# antipaparazzi.net
KiCad netlist of a schematic drawn in EAGLE
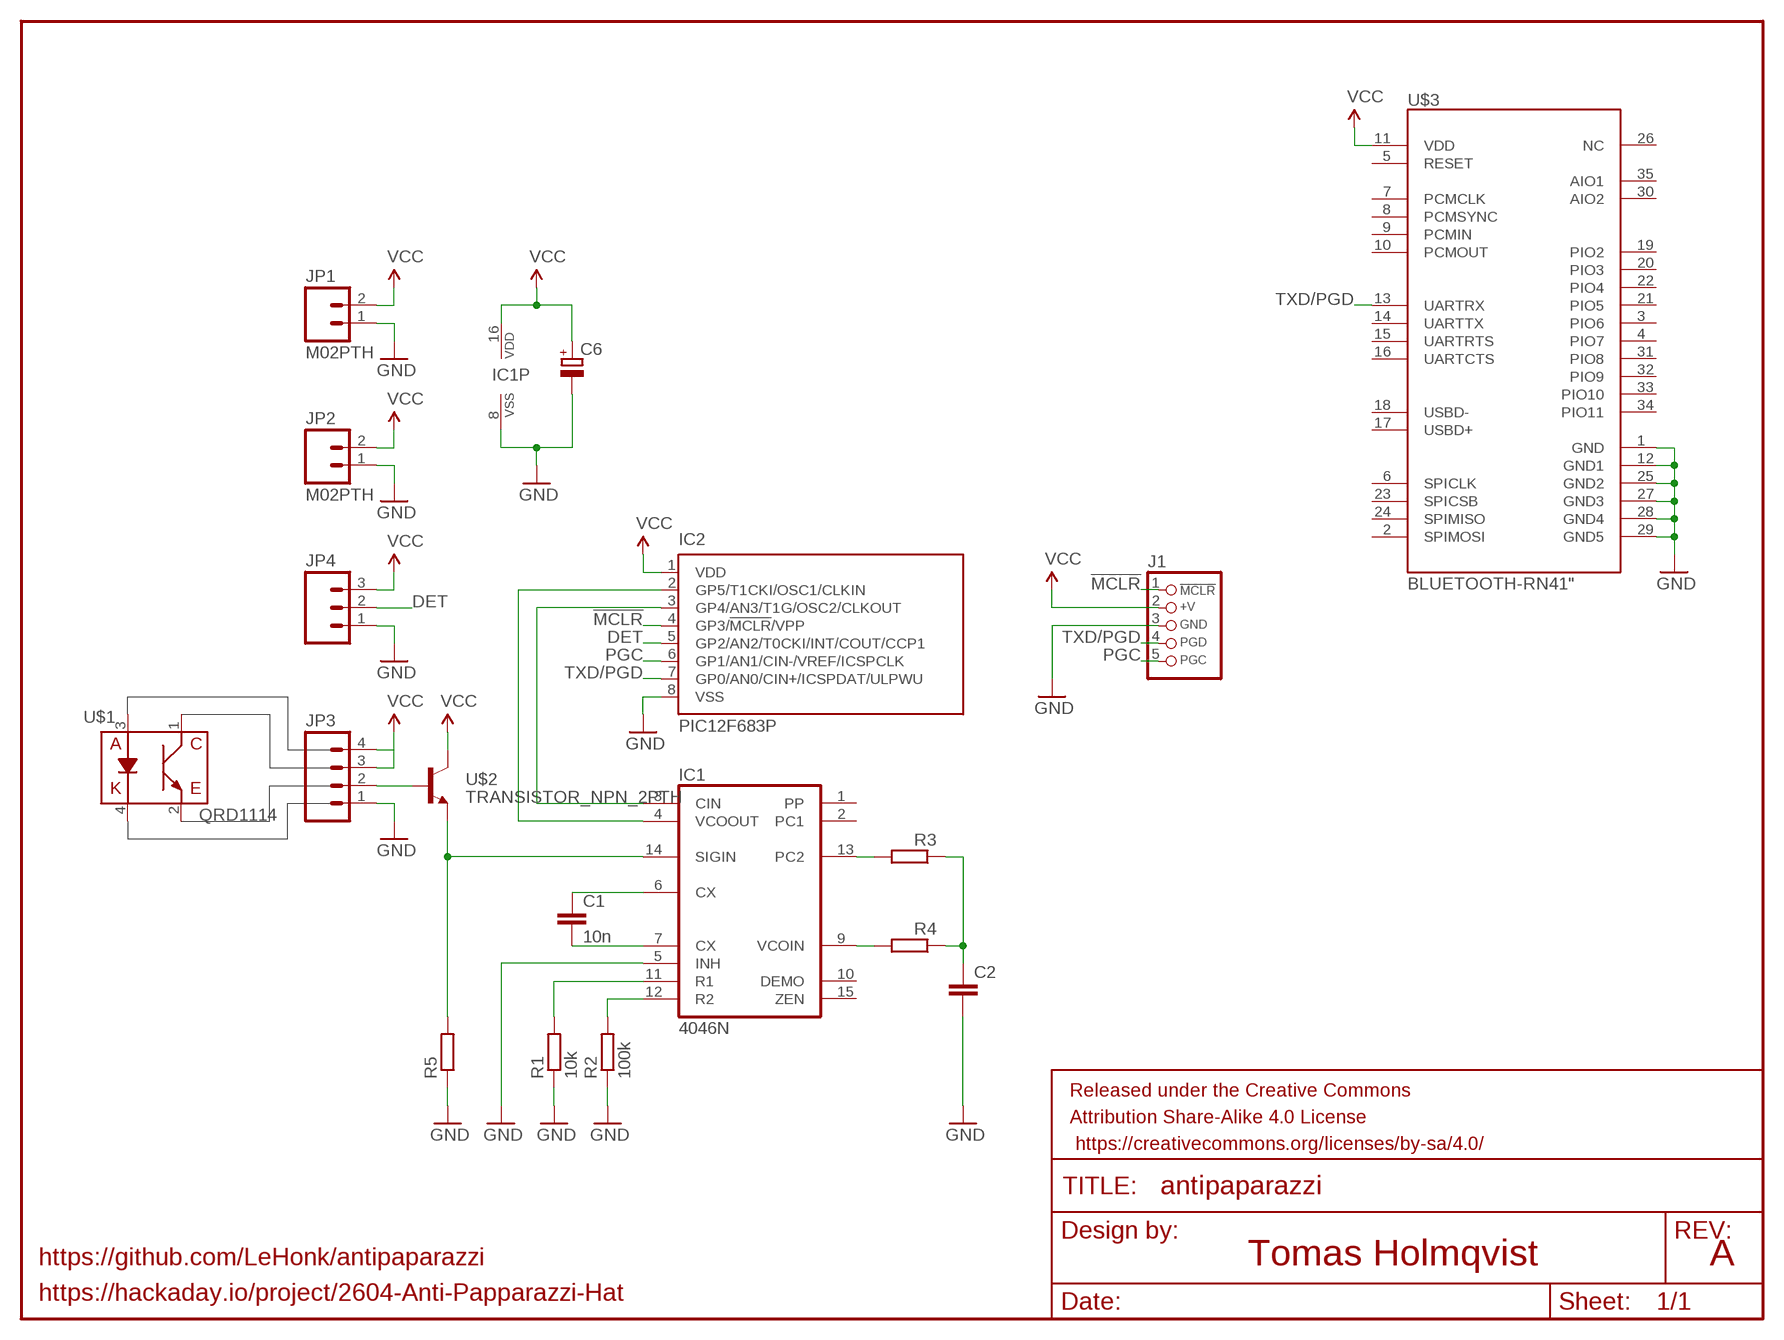
[diagram p0: schematic, sheet 1]

(export (version "E")
  (design (tool "Eeschema 10.0.6"))
  (components
    (comp (ref "C1")
      (value "10n")
      (footprint "eagle-import:C025_050-025X075")
      (libsource (lib "eagle-import") (part "C-EU025_050-025X075"))
    )
    (comp (ref "C2")
      (value "C-EU025_050-025X075")
      (footprint "eagle-import:C025_050-025X075")
      (libsource (lib "eagle-import") (part "C-EU025_050-025X075"))
    )
    (comp (ref "C6")
      (value "CPOL-EUE2.5-6")
      (footprint "eagle-import:E2,5-6")
      (libsource (lib "eagle-import") (part "CPOL-EUE2.5-6"))
    )
    (comp (ref "FRAME1")
      (value "FRAME-LETTER")
      (footprint "eagle-import:CREATIVE_COMMONS")
      (libsource (lib "eagle-import") (part "FRAME-LETTER"))
    )
    (comp (ref "IC1")
      (value "4046N")
      (footprint "eagle-import:DIL16")
      (libsource (lib "eagle-import") (part "4046N"))
    )
    (comp (ref "IC2")
      (value "PIC12F683P")
      (footprint "eagle-import:DIL8")
      (fields (field (name "MF") "MICROCHIP") (field (name "MPN") "PIC12F683-I/P"))
      (libsource (lib "eagle-import") (part "PIC12F683P"))
    )
    (comp (ref "J1")
      (value "CON_HEADER_PRG_PIC_ICSP0.1INCH_B")
      (footprint "eagle-import:HEADER_PRG_1X05_ICSP_B")
      (libsource (lib "eagle-import") (part "CON_HEADER_PRG_PIC_ICSP0.1INCH_B"))
    )
    (comp (ref "JP1")
      (value "M02PTH")
      (footprint "eagle-import:1X02")
      (libsource (lib "eagle-import") (part "M02PTH"))
    )
    (comp (ref "JP2")
      (value "M02PTH")
      (footprint "eagle-import:1X02")
      (libsource (lib "eagle-import") (part "M02PTH"))
    )
    (comp (ref "JP3")
      (value "M04PTH")
      (footprint "eagle-import:1X04")
      (libsource (lib "eagle-import") (part "M04PTH"))
    )
    (comp (ref "JP4")
      (value "M03PTH")
      (footprint "eagle-import:1X03")
      (libsource (lib "eagle-import") (part "M03PTH"))
    )
    (comp (ref "R1")
      (value "10k")
      (footprint "eagle-import:0207_2V")
      (libsource (lib "eagle-import") (part "R-EU_0207/2V"))
    )
    (comp (ref "R2")
      (value "100k")
      (footprint "eagle-import:0207_2V")
      (libsource (lib "eagle-import") (part "R-EU_0207/2V"))
    )
    (comp (ref "R3")
      (value "R-EU_0207/2V")
      (footprint "eagle-import:0207_2V")
      (libsource (lib "eagle-import") (part "R-EU_0207/2V"))
    )
    (comp (ref "R4")
      (value "R-EU_0207/2V")
      (footprint "eagle-import:0207_2V")
      (libsource (lib "eagle-import") (part "R-EU_0207/2V"))
    )
    (comp (ref "R5")
      (value "R-EU_0207/2V")
      (footprint "eagle-import:0207_2V")
      (libsource (lib "eagle-import") (part "R-EU_0207/2V"))
    )
    (comp (ref "U$1")
      (value "QRD1114")
      (footprint "eagle-import:QRD1114")
      (libsource (lib "eagle-import") (part "QRD1114"))
    )
    (comp (ref "U$2")
      (value "TRANSISTOR_NPN_2PTH")
      (footprint "eagle-import:TO-92")
      (libsource (lib "eagle-import") (part "TRANSISTOR_NPN_2PTH"))
    )
    (comp (ref "U$3")
      (value "BLUETOOTH-RN41\"")
      (footprint "eagle-import:RN41")
      (libsource (lib "eagle-import") (part "BLUETOOTH-RN41{dblquote}"))
    )
  )
  (nets
    (net (code "1") (name "/DET") (class "Default")
      (node (ref "IC2") (pin "5") (pinfunction "GP2/AN2/T0CKI/INT/COUT/CCP1_5") (pintype "bidirectional"))
      (node (ref "JP4") (pin "2") (pinfunction "2_2") (pintype "passive"))
    )
    (net (code "2") (name "/PGC") (class "Default")
      (node (ref "IC2") (pin "6") (pinfunction "GP1/AN1/CIN-/VREF/ICSPCLK_6") (pintype "bidirectional"))
      (node (ref "J1") (pin "5") (pinfunction "PGC_5") (pintype "passive"))
    )
    (net (code "3") (name "/TXD{slash}PGD") (class "Default")
      (node (ref "IC2") (pin "7") (pinfunction "GP0/AN0/CIN+/ICSPDAT/ULPWU_7") (pintype "bidirectional"))
      (node (ref "J1") (pin "4") (pinfunction "PGD_4") (pintype "passive"))
      (node (ref "U$3") (pin "13") (pinfunction "UARTRX_13") (pintype "bidirectional"))
    )
    (net (code "4") (name "/~{MCLR}") (class "Default")
      (node (ref "IC2") (pin "4") (pinfunction "GP3/~{MCLR}/VPP_4") (pintype "bidirectional"))
      (node (ref "J1") (pin "1") (pinfunction "/MCLR_1") (pintype "passive"))
    )
    (net (code "5") (name "GND") (class "Default")
      (node (ref "C2") (pin "2") (pinfunction "2_2") (pintype "passive"))
      (node (ref "C6") (pin "-") (pinfunction "-_-") (pintype "passive"))
      (node (ref "IC1") (pin "5") (pinfunction "INH_5") (pintype "input"))
      (node (ref "IC1") (pin "8") (pinfunction "VSS_8") (pintype "power_in"))
      (node (ref "IC2") (pin "8") (pinfunction "VSS_8") (pintype "power_in"))
      (node (ref "J1") (pin "3") (pinfunction "GND_3") (pintype "passive"))
      (node (ref "JP1") (pin "1") (pinfunction "1_1") (pintype "passive"))
      (node (ref "JP2") (pin "1") (pinfunction "1_1") (pintype "passive"))
      (node (ref "JP3") (pin "1") (pinfunction "1_1") (pintype "passive"))
      (node (ref "JP4") (pin "1") (pinfunction "1_1") (pintype "passive"))
      (node (ref "R1") (pin "1") (pinfunction "1_1") (pintype "passive"))
      (node (ref "R2") (pin "1") (pinfunction "1_1") (pintype "passive"))
      (node (ref "R5") (pin "1") (pinfunction "1_1") (pintype "passive"))
      (node (ref "U$3") (pin "1") (pinfunction "GND_1") (pintype "bidirectional"))
      (node (ref "U$3") (pin "12") (pinfunction "GND1_12") (pintype "bidirectional"))
      (node (ref "U$3") (pin "25") (pinfunction "GND2_25") (pintype "bidirectional"))
      (node (ref "U$3") (pin "27") (pinfunction "GND3_27") (pintype "bidirectional"))
      (node (ref "U$3") (pin "28") (pinfunction "GND4_28") (pintype "bidirectional"))
      (node (ref "U$3") (pin "29") (pinfunction "GND5_29") (pintype "bidirectional"))
    )
    (net (code "6") (name "Net-(C1-Pad1)") (class "Default")
      (node (ref "C1") (pin "1") (pinfunction "1_1") (pintype "passive"))
      (node (ref "IC1") (pin "6") (pinfunction "CX_6") (pintype "input"))
    )
    (net (code "7") (name "Net-(C1-Pad2)") (class "Default")
      (node (ref "C1") (pin "2") (pinfunction "2_2") (pintype "passive"))
      (node (ref "IC1") (pin "7") (pinfunction "CX_7") (pintype "input"))
    )
    (net (code "8") (name "Net-(C2-Pad1)") (class "Default")
      (node (ref "C2") (pin "1") (pinfunction "1_1") (pintype "passive"))
      (node (ref "R3") (pin "1") (pinfunction "1_1") (pintype "passive"))
      (node (ref "R4") (pin "1") (pinfunction "1_1") (pintype "passive"))
    )
    (net (code "9") (name "Net-(IC1A-CIN)") (class "Default")
      (node (ref "IC1") (pin "3") (pinfunction "CIN_3") (pintype "input"))
      (node (ref "IC2") (pin "3") (pinfunction "GP4/AN3/T1G/OSC2/CLKOUT_3") (pintype "bidirectional"))
    )
    (net (code "10") (name "Net-(IC1A-PC2)") (class "Default")
      (node (ref "IC1") (pin "13") (pinfunction "PC2_13") (pintype "output"))
      (node (ref "R3") (pin "2") (pinfunction "2_2") (pintype "passive"))
    )
    (net (code "11") (name "Net-(IC1A-R1)") (class "Default")
      (node (ref "IC1") (pin "11") (pinfunction "R1_11") (pintype "input"))
      (node (ref "R1") (pin "2") (pinfunction "2_2") (pintype "passive"))
    )
    (net (code "12") (name "Net-(IC1A-R2)") (class "Default")
      (node (ref "IC1") (pin "12") (pinfunction "R2_12") (pintype "input"))
      (node (ref "R2") (pin "2") (pinfunction "2_2") (pintype "passive"))
    )
    (net (code "13") (name "Net-(IC1A-SIGIN)") (class "Default")
      (node (ref "IC1") (pin "14") (pinfunction "SIGIN_14") (pintype "input"))
      (node (ref "R5") (pin "2") (pinfunction "2_2") (pintype "passive"))
      (node (ref "U$2") (pin "3") (pinfunction "E_3") (pintype "passive"))
    )
    (net (code "14") (name "Net-(IC1A-VCOIN)") (class "Default")
      (node (ref "IC1") (pin "9") (pinfunction "VCOIN_9") (pintype "input"))
      (node (ref "R4") (pin "2") (pinfunction "2_2") (pintype "passive"))
    )
    (net (code "15") (name "Net-(IC1A-VCOOUT)") (class "Default")
      (node (ref "IC1") (pin "4") (pinfunction "VCOOUT_4") (pintype "output"))
      (node (ref "IC2") (pin "2") (pinfunction "GP5/T1CKI/OSC1/CLKIN_2") (pintype "bidirectional"))
    )
    (net (code "16") (name "Net-(U$2-B)") (class "Default")
      (node (ref "JP3") (pin "2") (pinfunction "2_2") (pintype "passive"))
      (node (ref "U$2") (pin "2") (pinfunction "B_2") (pintype "passive"))
    )
    (net (code "17") (name "VCC") (class "Default")
      (node (ref "C6") (pin "+") (pinfunction "+_+") (pintype "passive"))
      (node (ref "IC1") (pin "16") (pinfunction "VDD_16") (pintype "power_in"))
      (node (ref "IC2") (pin "1") (pinfunction "VDD_1") (pintype "power_in"))
      (node (ref "J1") (pin "2") (pinfunction "+V_2") (pintype "passive"))
      (node (ref "JP1") (pin "2") (pinfunction "2_2") (pintype "passive"))
      (node (ref "JP2") (pin "2") (pinfunction "2_2") (pintype "passive"))
      (node (ref "JP3") (pin "3") (pinfunction "3_3") (pintype "passive"))
      (node (ref "JP3") (pin "4") (pinfunction "4_4") (pintype "passive"))
      (node (ref "JP4") (pin "3") (pinfunction "3_3") (pintype "passive"))
      (node (ref "U$2") (pin "1") (pinfunction "C_1") (pintype "passive"))
      (node (ref "U$3") (pin "11") (pinfunction "VDD_11") (pintype "bidirectional"))
    )
    (net (code "18") (name "unconnected-(IC1A-DEMO-Pad10)") (class "Default")
      (node (ref "IC1") (pin "10") (pinfunction "DEMO_10") (pintype "output"))
    )
    (net (code "19") (name "unconnected-(IC1A-PC1-Pad2)") (class "Default")
      (node (ref "IC1") (pin "2") (pinfunction "PC1_2") (pintype "output"))
    )
    (net (code "20") (name "unconnected-(IC1A-PP-Pad1)") (class "Default")
      (node (ref "IC1") (pin "1") (pinfunction "PP_1") (pintype "output"))
    )
    (net (code "21") (name "unconnected-(IC1A-ZEN-Pad15)") (class "Default")
      (node (ref "IC1") (pin "15") (pinfunction "ZEN_15") (pintype "input"))
    )
    (net (code "22") (name "unconnected-(U$1-A-Pad3)") (class "Default")
      (node (ref "U$1") (pin "3") (pinfunction "A_3") (pintype "bidirectional"))
    )
    (net (code "23") (name "unconnected-(U$1-C-Pad2)") (class "Default")
      (node (ref "U$1") (pin "2") (pinfunction "C_2") (pintype "bidirectional"))
    )
    (net (code "24") (name "unconnected-(U$1-E-Pad1)") (class "Default")
      (node (ref "U$1") (pin "1") (pinfunction "E_1") (pintype "bidirectional"))
    )
    (net (code "25") (name "unconnected-(U$1-K-Pad4)") (class "Default")
      (node (ref "U$1") (pin "4") (pinfunction "K_4") (pintype "bidirectional"))
    )
    (net (code "26") (name "unconnected-(U$3-AIO1-Pad35)") (class "Default")
      (node (ref "U$3") (pin "35") (pinfunction "AIO1_35") (pintype "bidirectional"))
    )
    (net (code "27") (name "unconnected-(U$3-AIO2-Pad30)") (class "Default")
      (node (ref "U$3") (pin "30") (pinfunction "AIO2_30") (pintype "bidirectional"))
    )
    (net (code "28") (name "unconnected-(U$3-NC-Pad26)") (class "Default")
      (node (ref "U$3") (pin "26") (pinfunction "NC_26") (pintype "bidirectional"))
    )
    (net (code "29") (name "unconnected-(U$3-PCMCLK-Pad7)") (class "Default")
      (node (ref "U$3") (pin "7") (pinfunction "PCMCLK_7") (pintype "bidirectional"))
    )
    (net (code "30") (name "unconnected-(U$3-PCMIN-Pad9)") (class "Default")
      (node (ref "U$3") (pin "9") (pinfunction "PCMIN_9") (pintype "bidirectional"))
    )
    (net (code "31") (name "unconnected-(U$3-PCMOUT-Pad10)") (class "Default")
      (node (ref "U$3") (pin "10") (pinfunction "PCMOUT_10") (pintype "bidirectional"))
    )
    (net (code "32") (name "unconnected-(U$3-PCMSYNC-Pad8)") (class "Default")
      (node (ref "U$3") (pin "8") (pinfunction "PCMSYNC_8") (pintype "bidirectional"))
    )
    (net (code "33") (name "unconnected-(U$3-PIO2-Pad19)") (class "Default")
      (node (ref "U$3") (pin "19") (pinfunction "PIO2_19") (pintype "bidirectional"))
    )
    (net (code "34") (name "unconnected-(U$3-PIO3-Pad20)") (class "Default")
      (node (ref "U$3") (pin "20") (pinfunction "PIO3_20") (pintype "bidirectional"))
    )
    (net (code "35") (name "unconnected-(U$3-PIO4-Pad22)") (class "Default")
      (node (ref "U$3") (pin "22") (pinfunction "PIO4_22") (pintype "bidirectional"))
    )
    (net (code "36") (name "unconnected-(U$3-PIO5-Pad21)") (class "Default")
      (node (ref "U$3") (pin "21") (pinfunction "PIO5_21") (pintype "bidirectional"))
    )
    (net (code "37") (name "unconnected-(U$3-PIO6-Pad3)") (class "Default")
      (node (ref "U$3") (pin "3") (pinfunction "PIO6_3") (pintype "bidirectional"))
    )
    (net (code "38") (name "unconnected-(U$3-PIO7-Pad4)") (class "Default")
      (node (ref "U$3") (pin "4") (pinfunction "PIO7_4") (pintype "bidirectional"))
    )
    (net (code "39") (name "unconnected-(U$3-PIO8-Pad31)") (class "Default")
      (node (ref "U$3") (pin "31") (pinfunction "PIO8_31") (pintype "bidirectional"))
    )
    (net (code "40") (name "unconnected-(U$3-PIO9-Pad32)") (class "Default")
      (node (ref "U$3") (pin "32") (pinfunction "PIO9_32") (pintype "bidirectional"))
    )
    (net (code "41") (name "unconnected-(U$3-PIO10-Pad33)") (class "Default")
      (node (ref "U$3") (pin "33") (pinfunction "PIO10_33") (pintype "bidirectional"))
    )
    (net (code "42") (name "unconnected-(U$3-PIO11-Pad34)") (class "Default")
      (node (ref "U$3") (pin "34") (pinfunction "PIO11_34") (pintype "bidirectional"))
    )
    (net (code "43") (name "unconnected-(U$3-RESET-Pad5)") (class "Default")
      (node (ref "U$3") (pin "5") (pinfunction "RESET_5") (pintype "bidirectional"))
    )
    (net (code "44") (name "unconnected-(U$3-SPICLK-Pad6)") (class "Default")
      (node (ref "U$3") (pin "6") (pinfunction "SPICLK_6") (pintype "bidirectional"))
    )
    (net (code "45") (name "unconnected-(U$3-SPICSB-Pad23)") (class "Default")
      (node (ref "U$3") (pin "23") (pinfunction "SPICSB_23") (pintype "bidirectional"))
    )
    (net (code "46") (name "unconnected-(U$3-SPIMISO-Pad24)") (class "Default")
      (node (ref "U$3") (pin "24") (pinfunction "SPIMISO_24") (pintype "bidirectional"))
    )
    (net (code "47") (name "unconnected-(U$3-SPIMOSI-Pad2)") (class "Default")
      (node (ref "U$3") (pin "2") (pinfunction "SPIMOSI_2") (pintype "bidirectional"))
    )
    (net (code "48") (name "unconnected-(U$3-UARTCTS-Pad16)") (class "Default")
      (node (ref "U$3") (pin "16") (pinfunction "UARTCTS_16") (pintype "bidirectional"))
    )
    (net (code "49") (name "unconnected-(U$3-UARTRTS-Pad15)") (class "Default")
      (node (ref "U$3") (pin "15") (pinfunction "UARTRTS_15") (pintype "bidirectional"))
    )
    (net (code "50") (name "unconnected-(U$3-UARTTX-Pad14)") (class "Default")
      (node (ref "U$3") (pin "14") (pinfunction "UARTTX_14") (pintype "bidirectional"))
    )
    (net (code "51") (name "unconnected-(U$3-USBD+-Pad17)") (class "Default")
      (node (ref "U$3") (pin "17") (pinfunction "USBD+_17") (pintype "bidirectional"))
    )
    (net (code "52") (name "unconnected-(U$3-USBD--Pad18)") (class "Default")
      (node (ref "U$3") (pin "18") (pinfunction "USBD-_18") (pintype "bidirectional"))
    )
  )
)
